# schematic.net
KiCad netlist of a schematic drawn in EAGLE
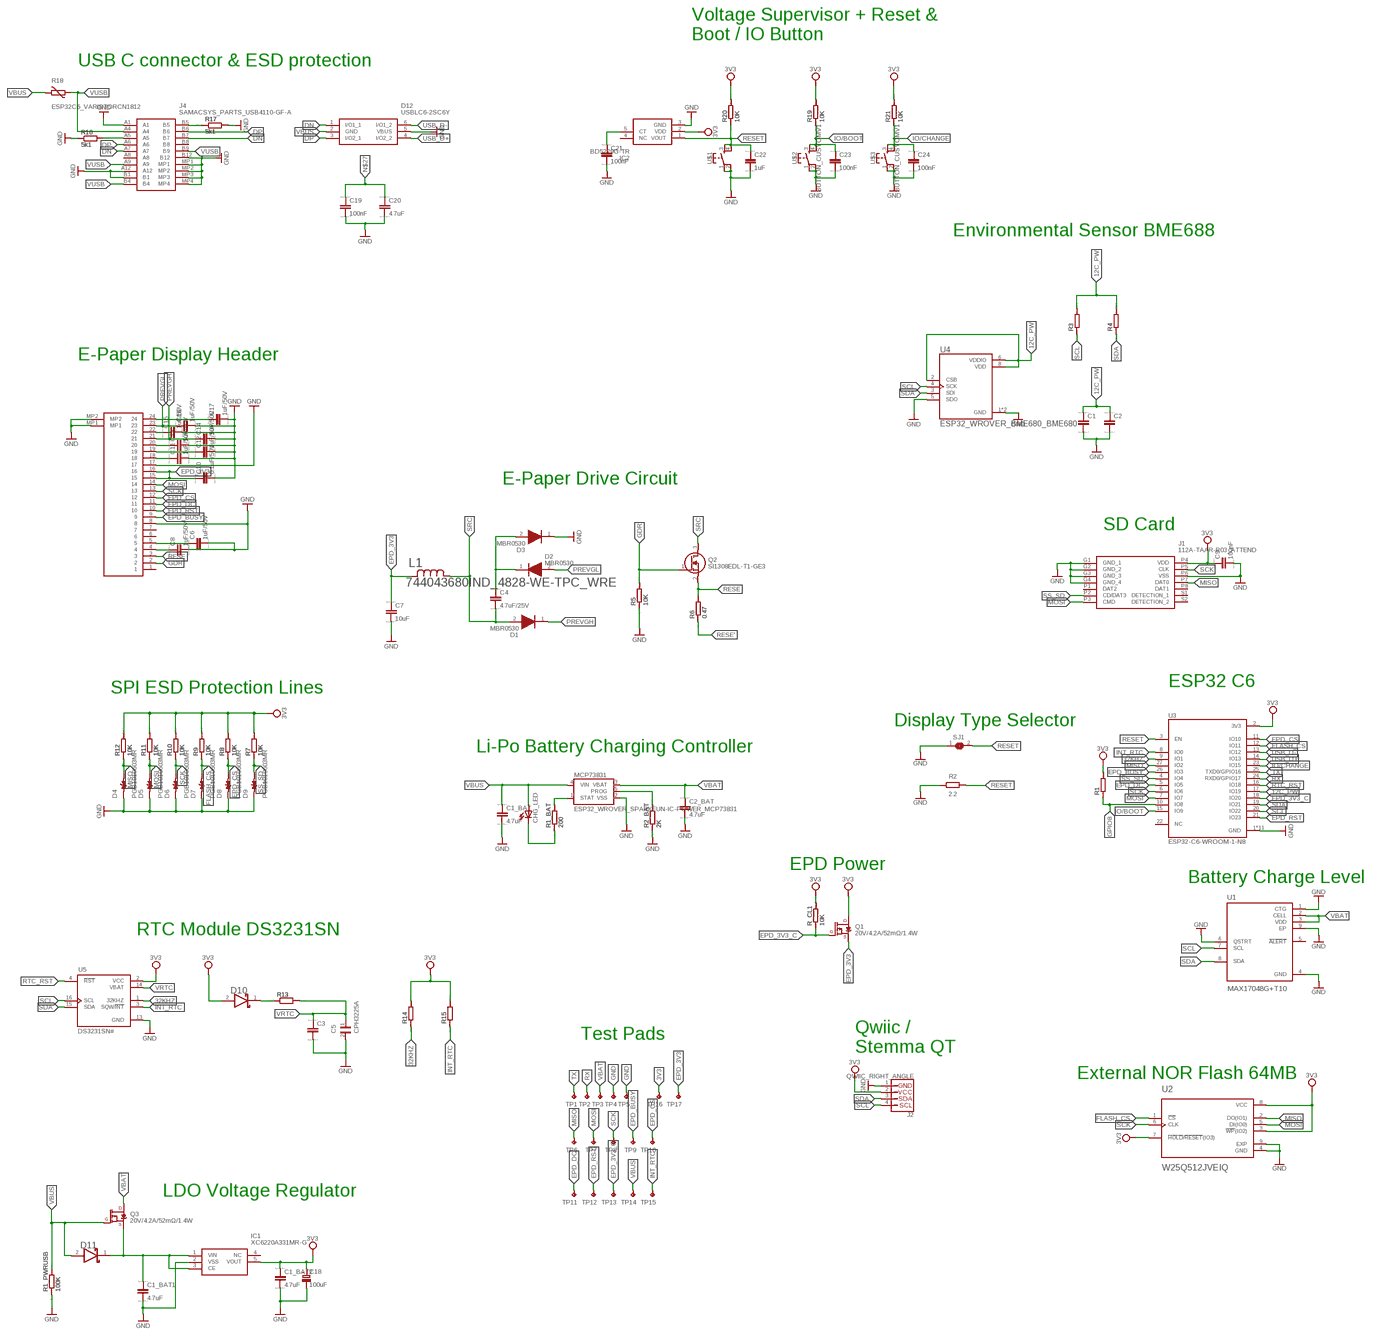
[diagram p0: schematic, sheet 1, overview]
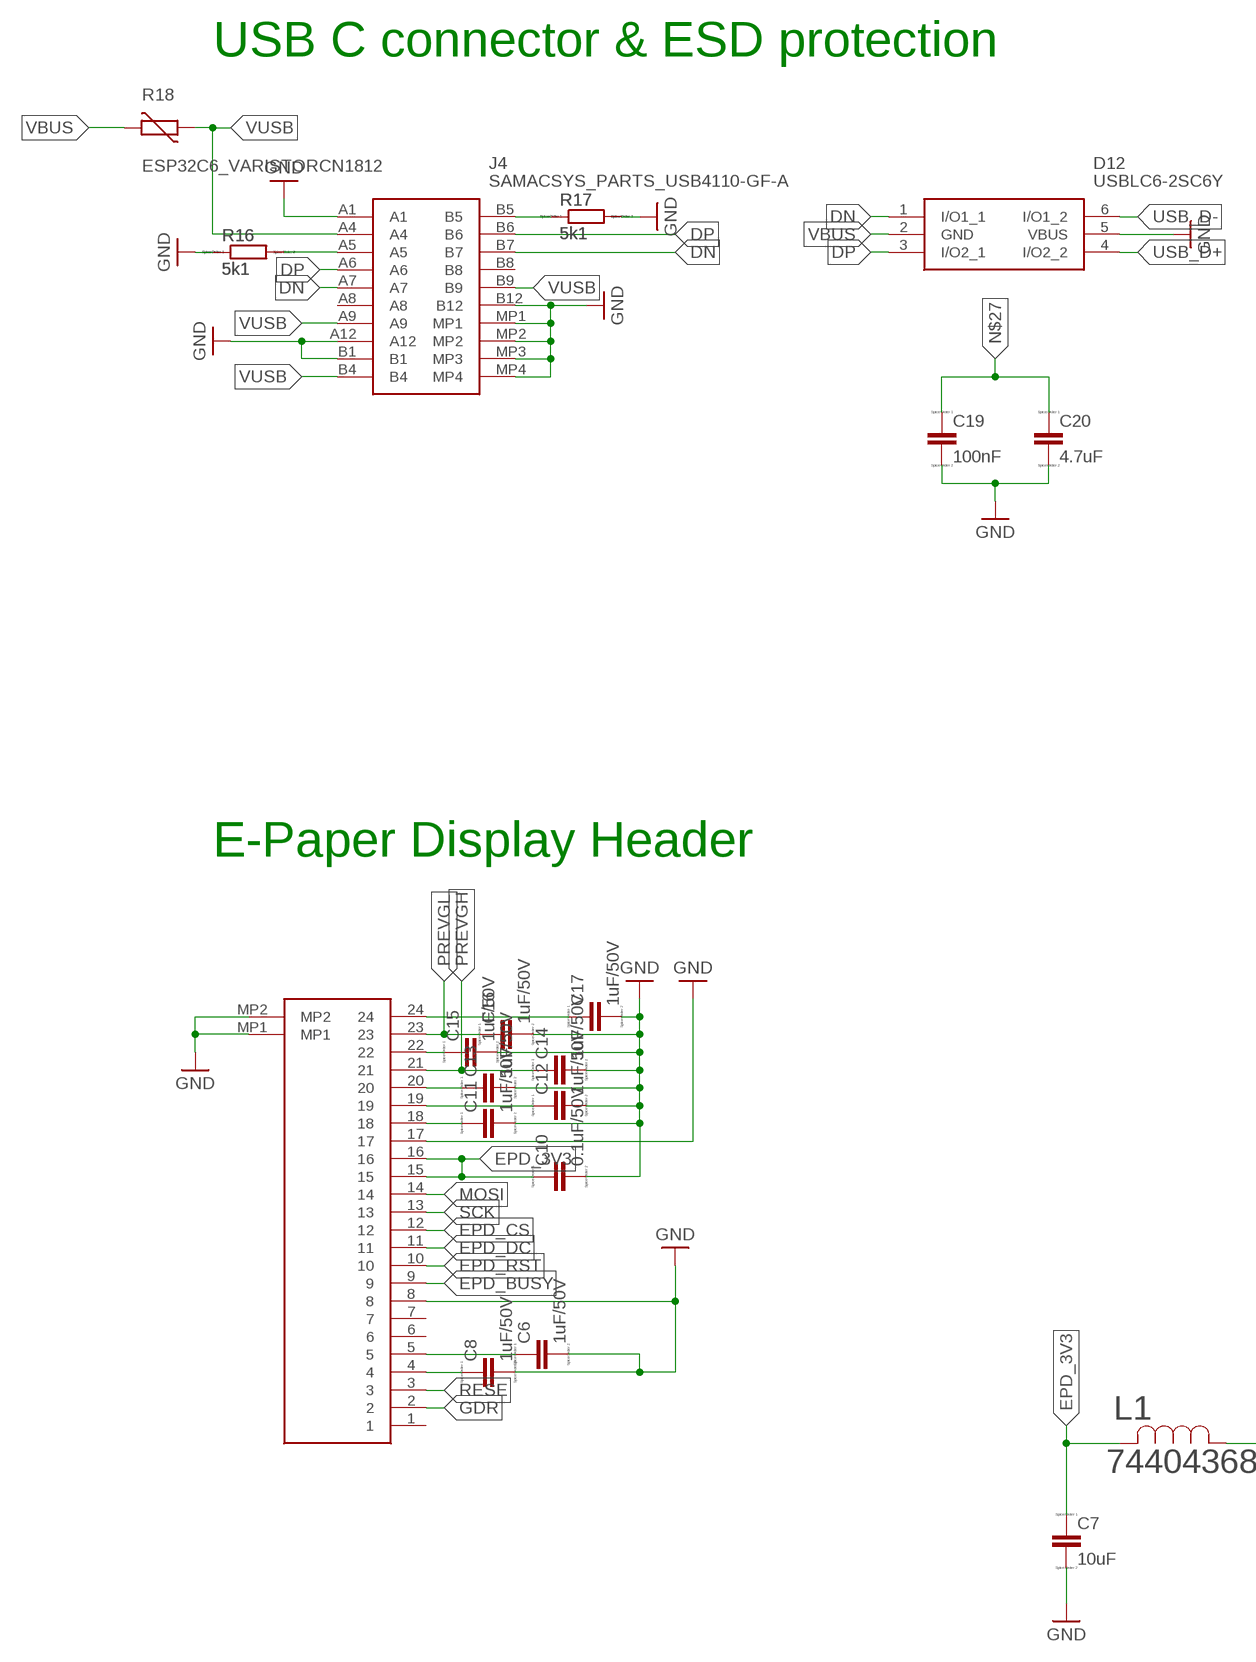
[diagram p1: schematic, sheet 1, part 1 of 4]
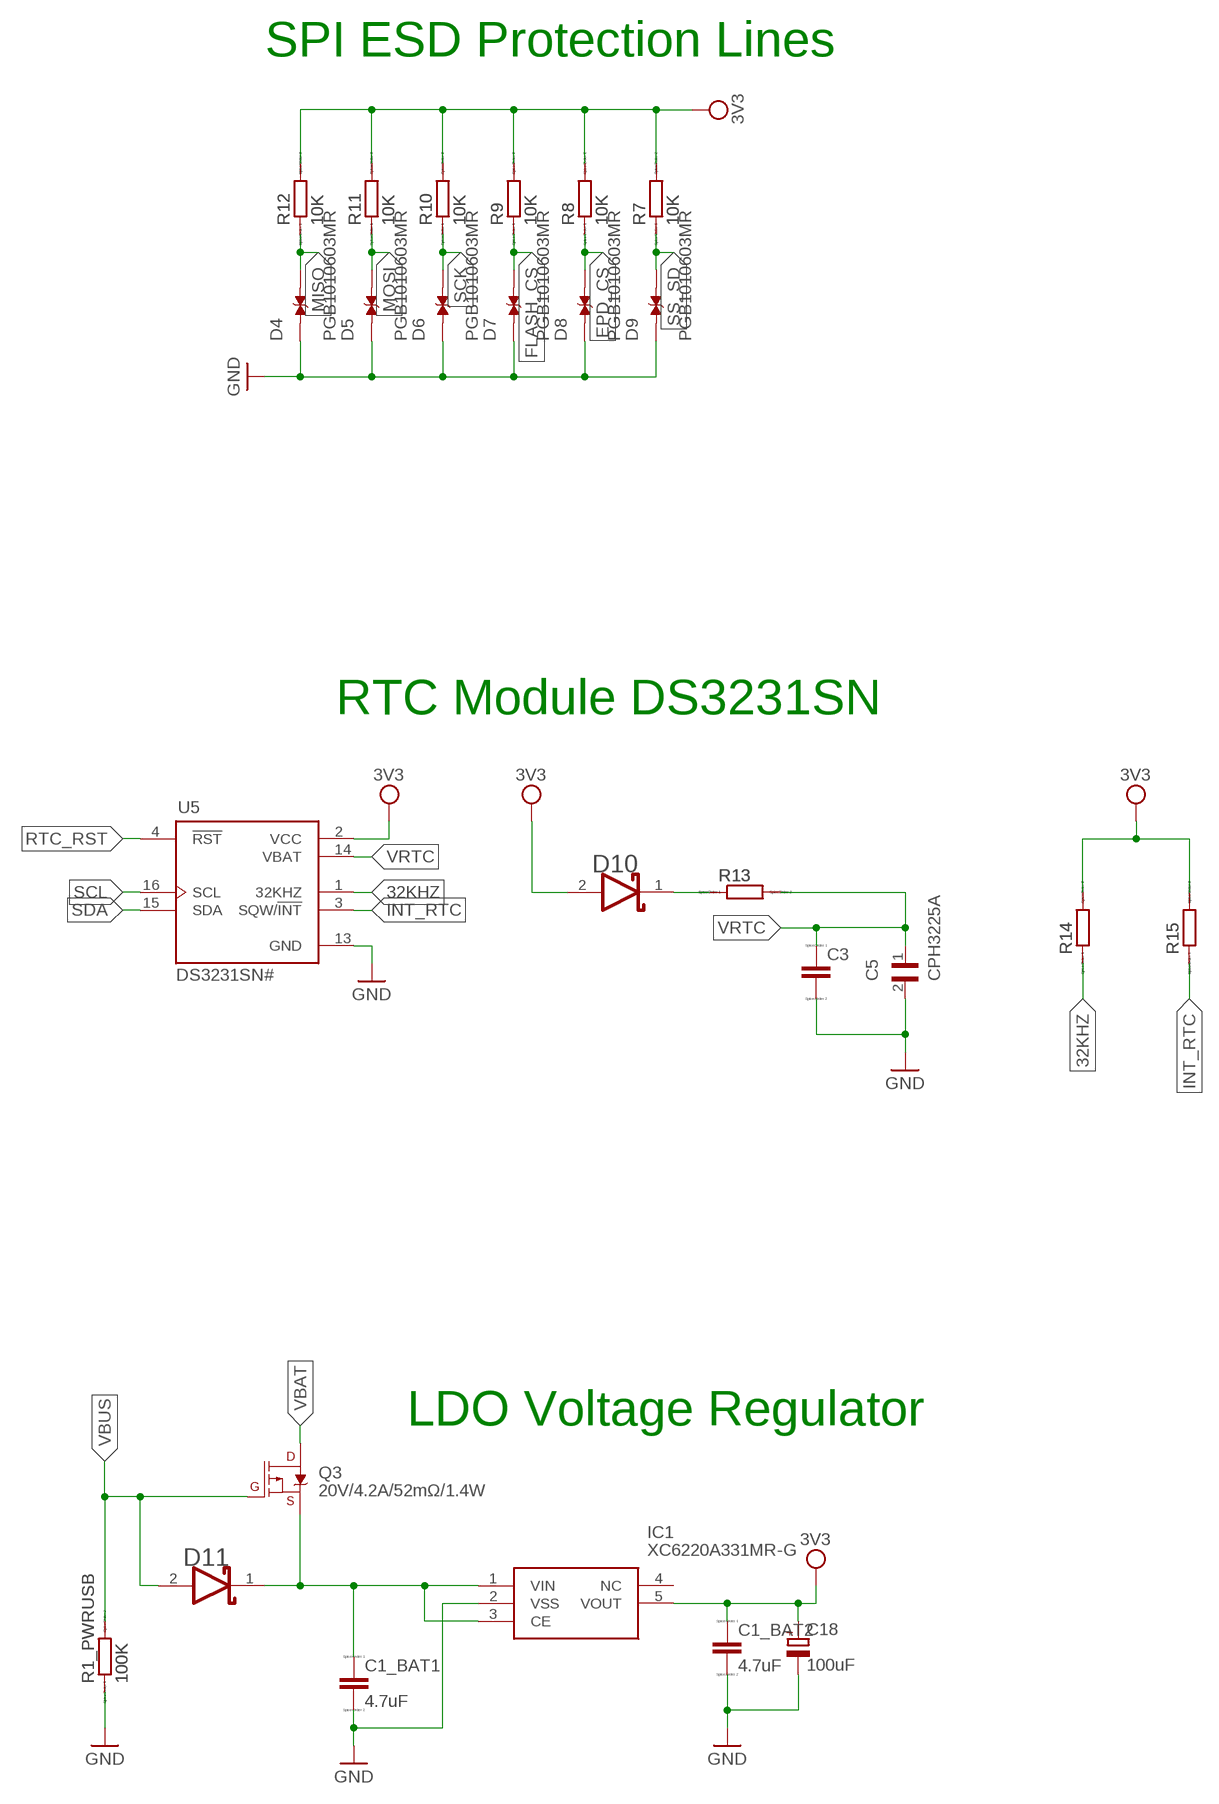
[diagram p2: schematic, sheet 1, part 2 of 4]
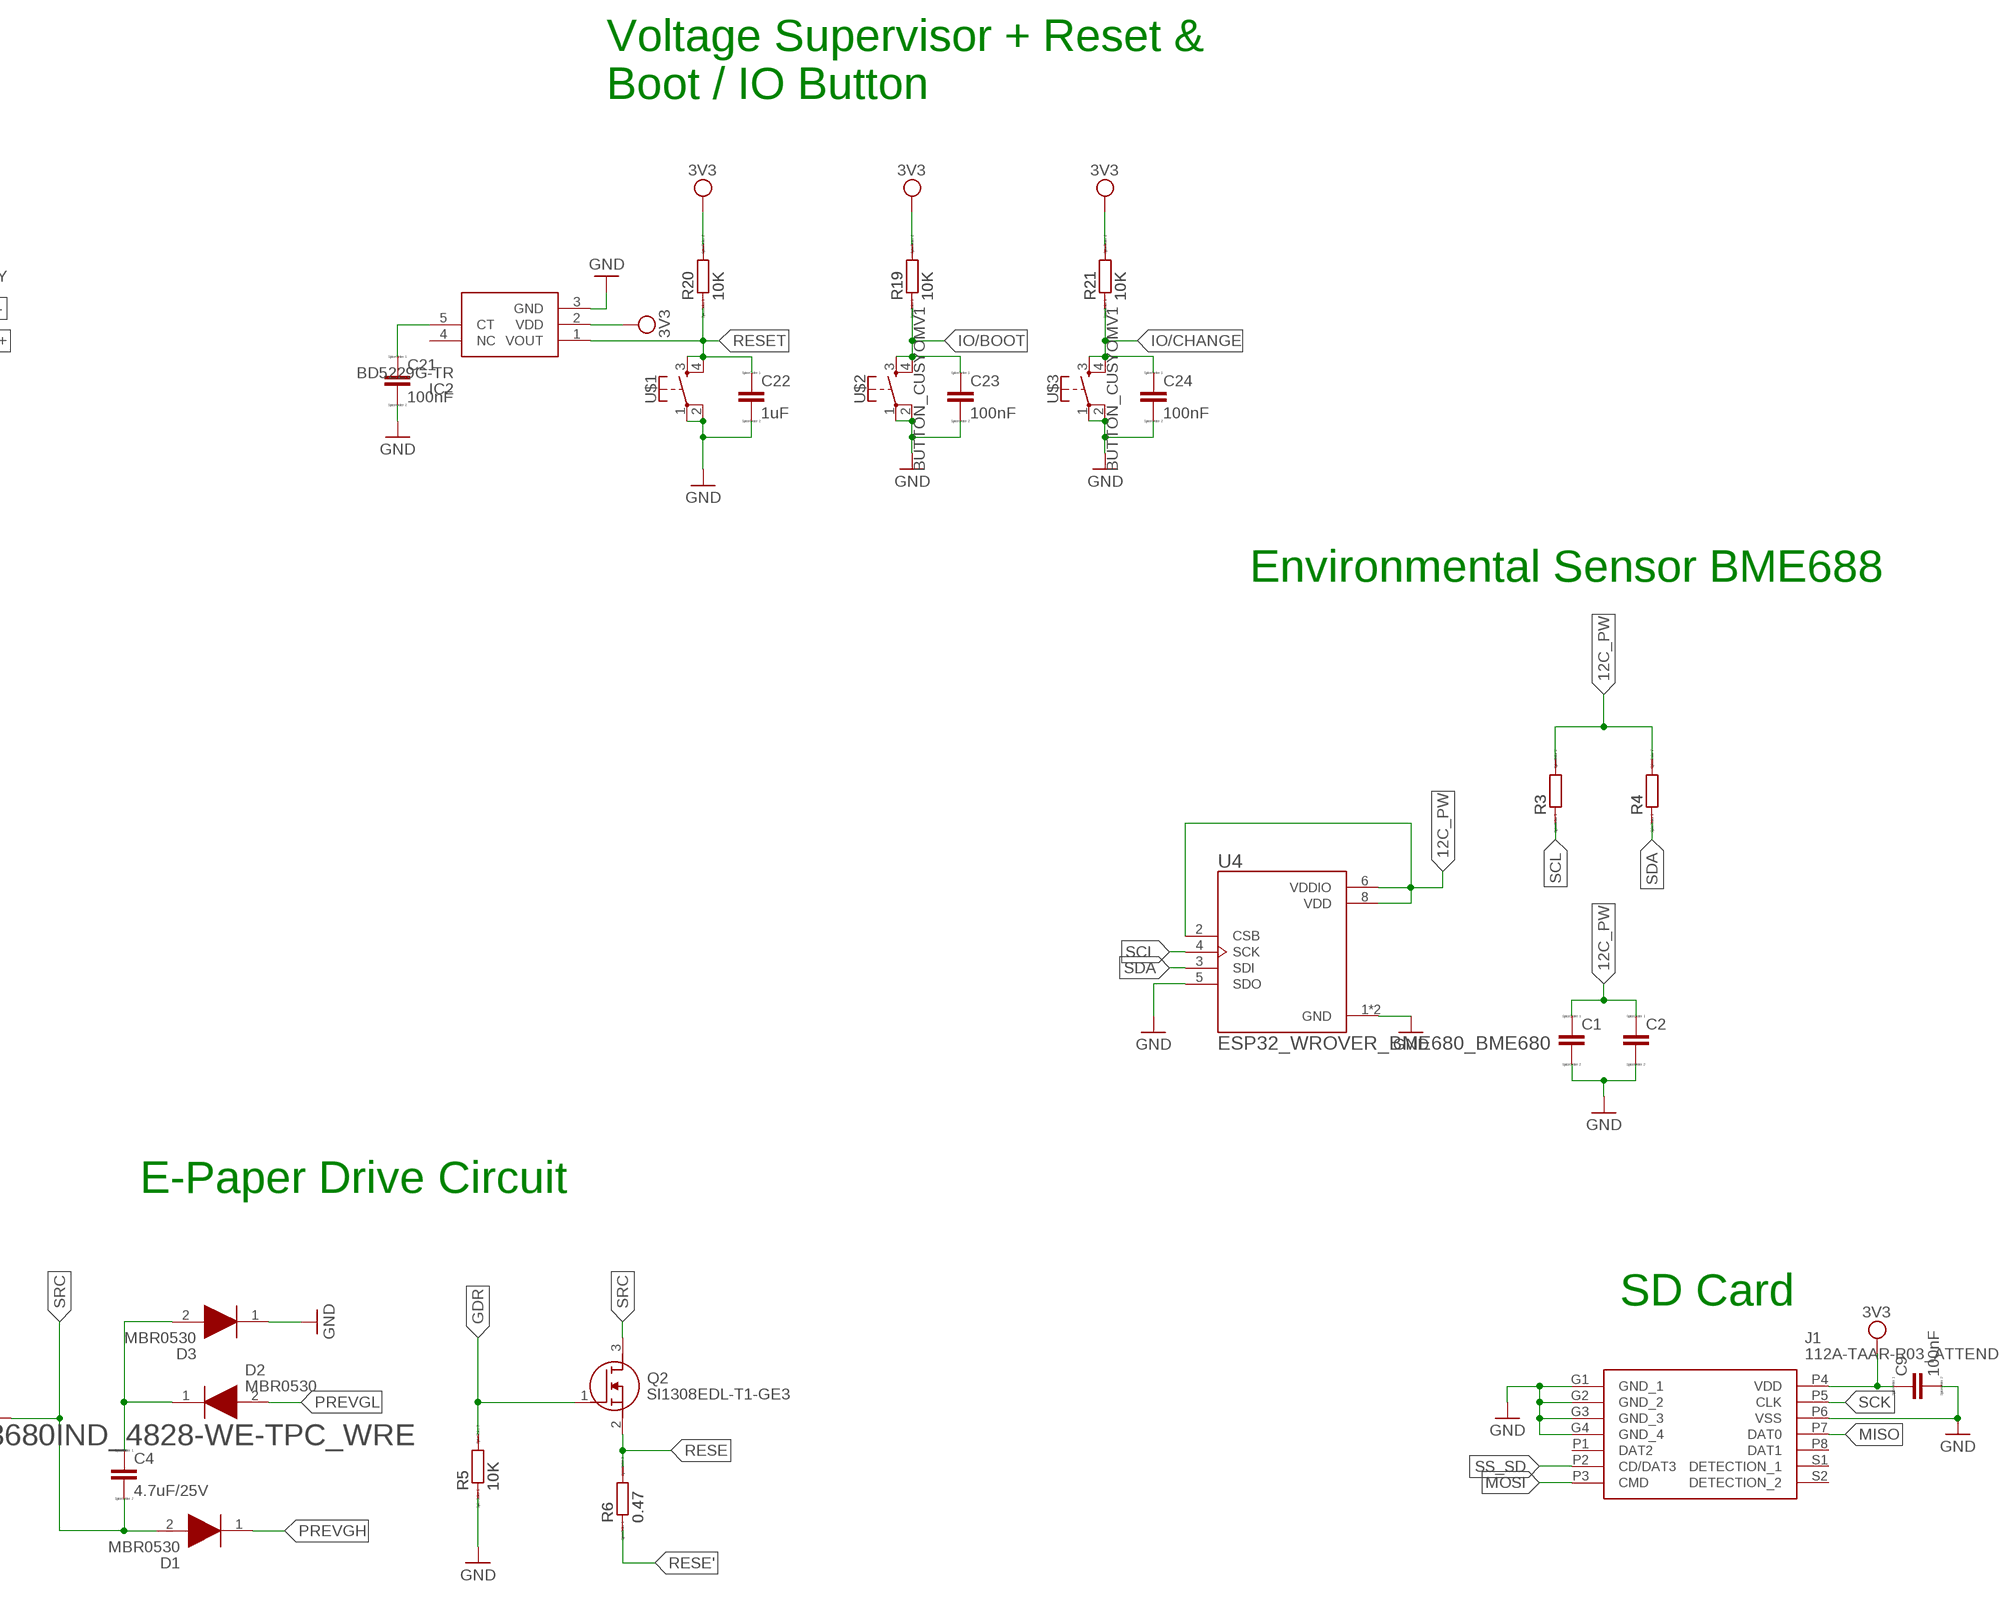
[diagram p3: schematic, sheet 1, part 3 of 4]
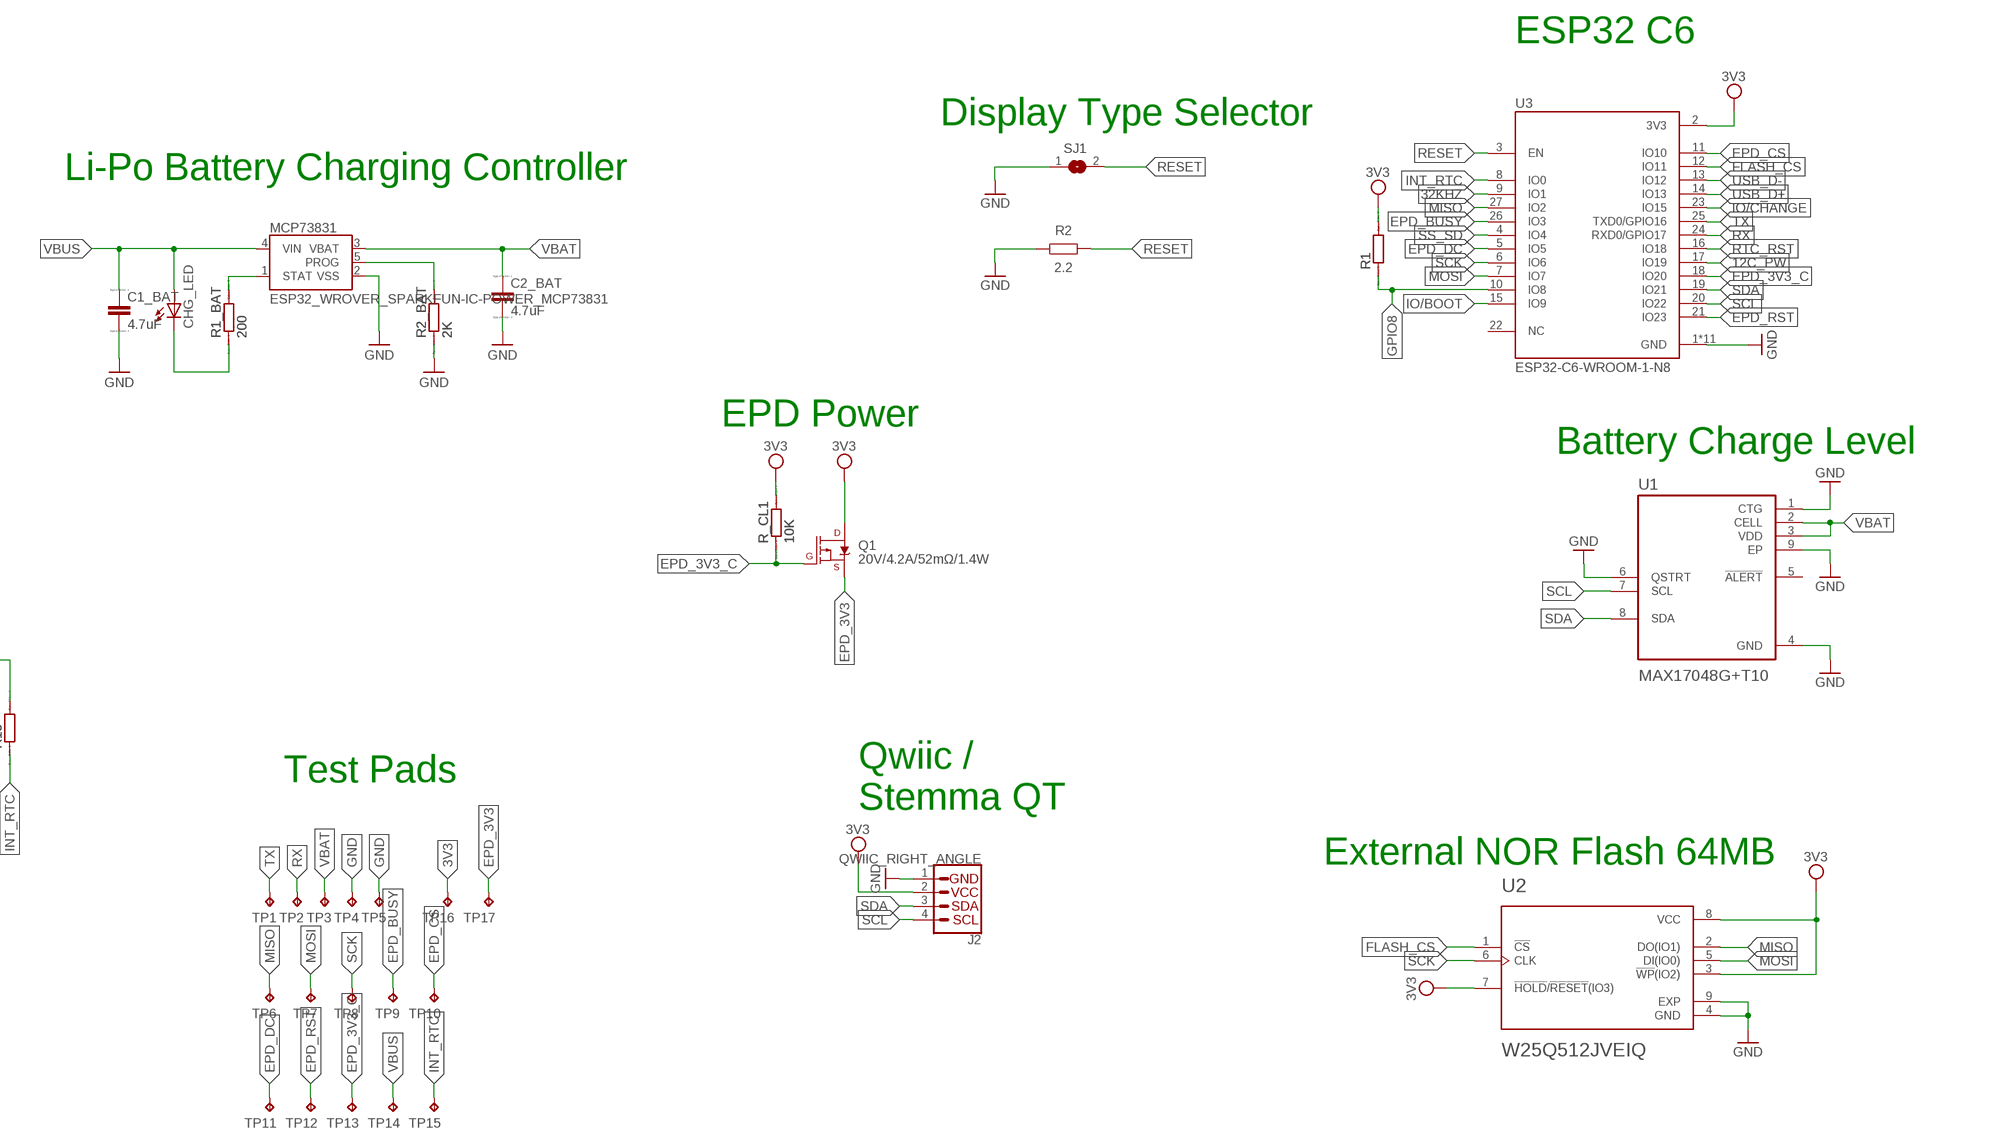
[diagram p4: schematic, sheet 1, part 4 of 4]

(export (version "E")
  (design (tool "Eeschema 10.0.6"))
  (components
    (comp (ref "C1")
      (value "ESP32_WROVER_EAGLE-LTSPICE_CC0402")
      (footprint "eagle-import:ESP32_WROVER_EAGLE-LTSPICE_C0402")
      (libsource (lib "eagle-import") (part "ESP32_WROVER_EAGLE-LTSPICE_CC0402"))
    )
    (comp (ref "C1_BAT")
      (value "4.7uF")
      (footprint "eagle-import:ESP32_WROVER_EAGLE-LTSPICE_C0402")
      (libsource (lib "eagle-import") (part "ESP32_WROVER_EAGLE-LTSPICE_CC0402"))
    )
    (comp (ref "C1_BAT1")
      (value "4.7uF")
      (footprint "eagle-import:ESP32_WROVER_EAGLE-LTSPICE_C0402")
      (libsource (lib "eagle-import") (part "ESP32_WROVER_EAGLE-LTSPICE_CC0402"))
    )
    (comp (ref "C1_BAT2")
      (value "4.7uF")
      (footprint "eagle-import:ESP32_WROVER_EAGLE-LTSPICE_C0402")
      (libsource (lib "eagle-import") (part "ESP32_WROVER_EAGLE-LTSPICE_CC0402"))
    )
    (comp (ref "C2")
      (value "ESP32_WROVER_EAGLE-LTSPICE_CC0402")
      (footprint "eagle-import:ESP32_WROVER_EAGLE-LTSPICE_C0402")
      (libsource (lib "eagle-import") (part "ESP32_WROVER_EAGLE-LTSPICE_CC0402"))
    )
    (comp (ref "C2_BAT")
      (value "4.7uF")
      (footprint "eagle-import:ESP32_WROVER_EAGLE-LTSPICE_C0402")
      (libsource (lib "eagle-import") (part "ESP32_WROVER_EAGLE-LTSPICE_CC0402"))
    )
    (comp (ref "C3")
      (value "EAGLE-LTSPICE_CC0402")
      (footprint "eagle-import:EAGLE-LTSPICE_C0402")
      (libsource (lib "eagle-import") (part "EAGLE-LTSPICE_CC0402"))
    )
    (comp (ref "C4")
      (value "4.7uF/25V")
      (footprint "eagle-import:EAGLE-LTSPICE_C0402")
      (libsource (lib "eagle-import") (part "EAGLE-LTSPICE_CC0402"))
    )
    (comp (ref "C5")
      (value "CPH3225A")
      (footprint "eagle-import:CAPCP3225X100N")
      (fields (field (name "MF") "Seiko Instruments"))
      (libsource (lib "eagle-import") (part "CPH3225A"))
    )
    (comp (ref "C6")
      (value "1uF/50V")
      (footprint "eagle-import:ESP32_WROVER_EAGLE-LTSPICE_C0402")
      (libsource (lib "eagle-import") (part "ESP32_WROVER_EAGLE-LTSPICE_CC0402"))
    )
    (comp (ref "C7")
      (value "10uF")
      (footprint "eagle-import:EAGLE-LTSPICE_C0402")
      (libsource (lib "eagle-import") (part "EAGLE-LTSPICE_CC0402"))
    )
    (comp (ref "C8")
      (value "1uF/50V")
      (footprint "eagle-import:ESP32_WROVER_EAGLE-LTSPICE_C0402")
      (libsource (lib "eagle-import") (part "ESP32_WROVER_EAGLE-LTSPICE_CC0402"))
    )
    (comp (ref "C9")
      (value "100nF")
      (footprint "eagle-import:EAGLE-LTSPICE_C0402")
      (libsource (lib "eagle-import") (part "EAGLE-LTSPICE_CC0402"))
    )
    (comp (ref "C10")
      (value "0.1uF/50V")
      (footprint "eagle-import:ESP32_WROVER_EAGLE-LTSPICE_C0402")
      (libsource (lib "eagle-import") (part "ESP32_WROVER_EAGLE-LTSPICE_CC0402"))
    )
    (comp (ref "C11")
      (value "1uF/50V")
      (footprint "eagle-import:ESP32_WROVER_EAGLE-LTSPICE_C0402")
      (libsource (lib "eagle-import") (part "ESP32_WROVER_EAGLE-LTSPICE_CC0402"))
    )
    (comp (ref "C12")
      (value "1uF/50V")
      (footprint "eagle-import:ESP32_WROVER_EAGLE-LTSPICE_C0402")
      (libsource (lib "eagle-import") (part "ESP32_WROVER_EAGLE-LTSPICE_CC0402"))
    )
    (comp (ref "C13")
      (value "1uF/50V")
      (footprint "eagle-import:ESP32_WROVER_EAGLE-LTSPICE_C0402")
      (libsource (lib "eagle-import") (part "ESP32_WROVER_EAGLE-LTSPICE_CC0402"))
    )
    (comp (ref "C14")
      (value "1uF/50V")
      (footprint "eagle-import:ESP32_WROVER_EAGLE-LTSPICE_C0402")
      (libsource (lib "eagle-import") (part "ESP32_WROVER_EAGLE-LTSPICE_CC0402"))
    )
    (comp (ref "C15")
      (value "1uF/50V")
      (footprint "eagle-import:ESP32_WROVER_EAGLE-LTSPICE_C0402")
      (libsource (lib "eagle-import") (part "ESP32_WROVER_EAGLE-LTSPICE_CC0402"))
    )
    (comp (ref "C16")
      (value "1uF/50V")
      (footprint "eagle-import:ESP32_WROVER_EAGLE-LTSPICE_C0402")
      (libsource (lib "eagle-import") (part "ESP32_WROVER_EAGLE-LTSPICE_CC0402"))
    )
    (comp (ref "C17")
      (value "1uF/50V")
      (footprint "eagle-import:ESP32_WROVER_EAGLE-LTSPICE_C0402")
      (libsource (lib "eagle-import") (part "ESP32_WROVER_EAGLE-LTSPICE_CC0402"))
    )
    (comp (ref "C18")
      (value "100uF")
      (footprint "eagle-import:RCL_CT3528")
      (libsource (lib "eagle-import") (part "RCL_CPOL-EUCT3528"))
    )
    (comp (ref "C19")
      (value "100nF")
      (footprint "eagle-import:ESP32_WROVER_EAGLE-LTSPICE_C0402")
      (libsource (lib "eagle-import") (part "ESP32_WROVER_EAGLE-LTSPICE_CC0402"))
    )
    (comp (ref "C20")
      (value "4.7uF")
      (footprint "eagle-import:ESP32_WROVER_EAGLE-LTSPICE_C0402")
      (libsource (lib "eagle-import") (part "ESP32_WROVER_EAGLE-LTSPICE_CC0402"))
    )
    (comp (ref "C21")
      (value "100nF")
      (footprint "eagle-import:ESP32_WROVER_EAGLE-LTSPICE_C0402")
      (libsource (lib "eagle-import") (part "ESP32_WROVER_EAGLE-LTSPICE_CC0402"))
    )
    (comp (ref "C22")
      (value "1uF")
      (footprint "eagle-import:ESP32_WROVER_EAGLE-LTSPICE_C0402")
      (libsource (lib "eagle-import") (part "ESP32_WROVER_EAGLE-LTSPICE_CC0402"))
    )
    (comp (ref "C23")
      (value "100nF")
      (footprint "eagle-import:ESP32_WROVER_EAGLE-LTSPICE_C0402")
      (libsource (lib "eagle-import") (part "ESP32_WROVER_EAGLE-LTSPICE_CC0402"))
    )
    (comp (ref "C24")
      (value "100nF")
      (footprint "eagle-import:ESP32_WROVER_EAGLE-LTSPICE_C0402")
      (libsource (lib "eagle-import") (part "ESP32_WROVER_EAGLE-LTSPICE_CC0402"))
    )
    (comp (ref "CHG_LED")
      (value "ADAFRUIT_LEDCHIP-LED0603")
      (footprint "eagle-import:ADAFRUIT_CHIP-LED0603")
      (libsource (lib "eagle-import") (part "ADAFRUIT_LEDCHIP-LED0603"))
    )
    (comp (ref "D1")
      (value "MBR0530")
      (footprint "eagle-import:SOD3716X135N")
      (fields (field (name "MF") "ON Semiconductor"))
      (libsource (lib "eagle-import") (part "MBR0530"))
    )
    (comp (ref "D2")
      (value "MBR0530")
      (footprint "eagle-import:SOD3716X135N")
      (fields (field (name "MF") "ON Semiconductor"))
      (libsource (lib "eagle-import") (part "MBR0530"))
    )
    (comp (ref "D3")
      (value "MBR0530")
      (footprint "eagle-import:SOD3716X135N")
      (fields (field (name "MF") "ON Semiconductor"))
      (libsource (lib "eagle-import") (part "MBR0530"))
    )
    (comp (ref "D4")
      (value "PGB1010603MR")
      (footprint "eagle-import:DIOC1608X36N")
      (fields (field (name "MF") "Littelfuse Inc."))
      (libsource (lib "eagle-import") (part "PGB1010603MR"))
    )
    (comp (ref "D5")
      (value "PGB1010603MR")
      (footprint "eagle-import:DIOC1608X36N")
      (fields (field (name "MF") "Littelfuse Inc."))
      (libsource (lib "eagle-import") (part "PGB1010603MR"))
    )
    (comp (ref "D6")
      (value "PGB1010603MR")
      (footprint "eagle-import:DIOC1608X36N")
      (fields (field (name "MF") "Littelfuse Inc."))
      (libsource (lib "eagle-import") (part "PGB1010603MR"))
    )
    (comp (ref "D7")
      (value "PGB1010603MR")
      (footprint "eagle-import:DIOC1608X36N")
      (fields (field (name "MF") "Littelfuse Inc."))
      (libsource (lib "eagle-import") (part "PGB1010603MR"))
    )
    (comp (ref "D8")
      (value "PGB1010603MR")
      (footprint "eagle-import:DIOC1608X36N")
      (fields (field (name "MF") "Littelfuse Inc."))
      (libsource (lib "eagle-import") (part "PGB1010603MR"))
    )
    (comp (ref "D9")
      (value "PGB1010603MR")
      (footprint "eagle-import:DIOC1608X36N")
      (fields (field (name "MF") "Littelfuse Inc."))
      (libsource (lib "eagle-import") (part "PGB1010603MR"))
    )
    (comp (ref "D10")
      (value "ESP32_WROVER_AVX---SD0805S020S1R0_AVX_SD0805S020S1R0_0_0AVX_SD0805S020S1R0_0_0")
      (footprint "eagle-import:ESP32_WROVER_AVX---SD0805S020S1R0_AVX_SD0805S020S1R0_0")
      (fields
        (field (name "DIGIKEY_PART_NUMBER") "478-7800-1-ND")
        (field (name "MF") "AVX")
        (field (name "MOUSER_PART_NUMBER") "581-SD0805S020S1R0")
      )
      (libsource (lib "eagle-import") (part "ESP32_WROVER_AVX---SD0805S020S1R0_AVX_SD0805S020S1R0_0_0AVX_SD0805S020S1R0_0_0"))
    )
    (comp (ref "D11")
      (value "ESP32_WROVER_AVX---SD0805S020S1R0_AVX_SD0805S020S1R0_0_0AVX_SD0805S020S1R0_0_0")
      (footprint "eagle-import:ESP32_WROVER_AVX---SD0805S020S1R0_AVX_SD0805S020S1R0_0")
      (fields
        (field (name "DIGIKEY_PART_NUMBER") "478-7800-1-ND")
        (field (name "MF") "AVX")
        (field (name "MOUSER_PART_NUMBER") "581-SD0805S020S1R0")
      )
      (libsource (lib "eagle-import") (part "ESP32_WROVER_AVX---SD0805S020S1R0_AVX_SD0805S020S1R0_0_0AVX_SD0805S020S1R0_0_0"))
    )
    (comp (ref "D12")
      (value "USBLC6-2SC6Y")
      (footprint "eagle-import:SOT95P280X145-6N")
      (fields (field (name "MF") "STMicroelectronics"))
      (libsource (lib "eagle-import") (part "USBLC6-2SC6Y"))
    )
    (comp (ref "IC1")
      (value "XC6220A331MR-G")
      (footprint "eagle-import:SOT95P280X120-5N")
      (fields (field (name "MOUSER_PART_NUMBER") "865-XC6220A331MR-G"))
      (libsource (lib "eagle-import") (part "XC6220A331MR-G"))
    )
    (comp (ref "IC2")
      (value "BD5229G-TR")
      (footprint "eagle-import:SOT95P280X125-5N")
      (fields (field (name "MOUSER_PART_NUMBER") "755-BD5229G-TR"))
      (libsource (lib "eagle-import") (part "BD5229G-TR"))
    )
    (comp (ref "J1")
      (value "112A-TAAR-R03_ATTEND")
      (footprint "eagle-import:112ATAARR03ATTEND")
      (fields (field (name "MANUFACTURER_PART_NUMBER") "112A-TAAR-R03 ATTEND"))
      (libsource (lib "eagle-import") (part "112A-TAAR-R03_ATTEND"))
    )
    (comp (ref "J2")
      (value "QWIIC_RIGHT_ANGLE")
      (footprint "eagle-import:JST04_1MM_RA")
      (libsource (lib "eagle-import") (part "QWIIC_CONNECTORJS-1MM"))
    )
    (comp (ref "J3")
      (value "FH34SRJ-24S-0.5SH_99_")
      (footprint "eagle-import:FH34SRJ24S05SH99")
      (fields
        (field (name "MANUFACTURER_PART_NUMBER") "FH34SRJ-24S-0.5SH(99)")
        (field (name "MOUSER_PART_NUMBER") "798-FH34SRJ24S05SH99")
      )
      (libsource (lib "eagle-import") (part "FH34SRJ-24S-0.5SH_99_"))
    )
    (comp (ref "J4")
      (value "SAMACSYS_PARTS_USB4110-GF-A")
      (footprint "eagle-import:SAMACSYS_PARTS_USB4110GFA")
      (fields
        (field (name "MANUFACTURER_PART_NUMBER") "USB4110-GF-A")
        (field (name "MOUSER_PART_NUMBER") "640-USB4110-GF-A")
      )
      (libsource (lib "eagle-import") (part "SAMACSYS_PARTS_USB4110-GF-A"))
    )
    (comp (ref "L1")
      (value "744043680IND_4828-WE-TPC_WRE")
      (footprint "eagle-import:IND_4828-WE-TPC_WRE")
      (fields
        (field (name "MANUFACTURER_PART_NUMBER") "744043680")
        (field (name "COPYRIGHT") "Copyright (C) 2024 Ultra Librarian. All rights reserved.")
      )
      (libsource (lib "eagle-import") (part "744043680IND_4828-WE-TPC_WRE"))
    )
    (comp (ref "MCP73831")
      (value "ESP32_WROVER_SPARKFUN-IC-POWER_MCP73831")
      (footprint "eagle-import:ESP32_WROVER_SPARKFUN-IC-POWER_SOT23-5")
      (libsource (lib "eagle-import") (part "ESP32_WROVER_SPARKFUN-IC-POWER_MCP73831"))
    )
    (comp (ref "Q1")
      (value "20V/4.2A/52mΩ/1.4W")
      (footprint "eagle-import:ESP32_WROVER_SPARKFUN-DISCRETESEMI_SOT23-3")
      (libsource (lib "eagle-import") (part "ESP32_WROVER_SPARKFUN-DISCRETESEMI_MOSFET_PCH-DMG2305UX-7"))
    )
    (comp (ref "Q2")
      (value "SI1308EDL-T1-GE3")
      (footprint "eagle-import:SOT65P210X110-3N")
      (fields (field (name "MF") "Vishay Siliconix"))
      (libsource (lib "eagle-import") (part "SI1308EDL-T1-GE3"))
    )
    (comp (ref "Q3")
      (value "20V/4.2A/52mΩ/1.4W")
      (footprint "eagle-import:ESP32_WROVER_SPARKFUN-DISCRETESEMI_SOT23-3")
      (libsource (lib "eagle-import") (part "ESP32_WROVER_SPARKFUN-DISCRETESEMI_MOSFET_PCH-DMG2305UX-7"))
    )
    (comp (ref "R1")
      (value "ESP32_WROVER_EAGLE-LTSPICE_RR0402")
      (footprint "eagle-import:ESP32_WROVER_EAGLE-LTSPICE_R0402")
      (libsource (lib "eagle-import") (part "ESP32_WROVER_EAGLE-LTSPICE_RR0402"))
    )
    (comp (ref "R1_BAT")
      (value "200")
      (footprint "eagle-import:ESP32_WROVER_EAGLE-LTSPICE_R0402")
      (libsource (lib "eagle-import") (part "ESP32_WROVER_EAGLE-LTSPICE_RR0402"))
    )
    (comp (ref "R1_PWRUSB")
      (value "100K")
      (footprint "eagle-import:ESP32_WROVER_EAGLE-LTSPICE_R0402")
      (libsource (lib "eagle-import") (part "ESP32_WROVER_EAGLE-LTSPICE_RR0402"))
    )
    (comp (ref "R2")
      (value "2.2")
      (footprint "eagle-import:RESC1005X40")
      (libsource (lib "eagle-import") (part "RCHIP-0402(1005-METRIC)_"))
    )
    (comp (ref "R2_BAT")
      (value "2K")
      (footprint "eagle-import:ESP32_WROVER_EAGLE-LTSPICE_R0402")
      (libsource (lib "eagle-import") (part "ESP32_WROVER_EAGLE-LTSPICE_RR0402"))
    )
    (comp (ref "R3")
      (value "ESP32_WROVER_EAGLE-LTSPICE_RR0402")
      (footprint "eagle-import:ESP32_WROVER_EAGLE-LTSPICE_R0402")
      (libsource (lib "eagle-import") (part "ESP32_WROVER_EAGLE-LTSPICE_RR0402"))
    )
    (comp (ref "R4")
      (value "ESP32_WROVER_EAGLE-LTSPICE_RR0402")
      (footprint "eagle-import:ESP32_WROVER_EAGLE-LTSPICE_R0402")
      (libsource (lib "eagle-import") (part "ESP32_WROVER_EAGLE-LTSPICE_RR0402"))
    )
    (comp (ref "R5")
      (value "10K")
      (footprint "eagle-import:ESP32_WROVER_EAGLE-LTSPICE_R0402")
      (libsource (lib "eagle-import") (part "ESP32_WROVER_EAGLE-LTSPICE_RR0402"))
    )
    (comp (ref "R6")
      (value "0.47")
      (footprint "eagle-import:ESP32_WROVER_EAGLE-LTSPICE_R0402")
      (libsource (lib "eagle-import") (part "ESP32_WROVER_EAGLE-LTSPICE_RR0402"))
    )
    (comp (ref "R7")
      (value "10K")
      (footprint "eagle-import:ESP32_WROVER_EAGLE-LTSPICE_R0402")
      (libsource (lib "eagle-import") (part "ESP32_WROVER_EAGLE-LTSPICE_RR0402"))
    )
    (comp (ref "R8")
      (value "10K")
      (footprint "eagle-import:ESP32_WROVER_EAGLE-LTSPICE_R0402")
      (libsource (lib "eagle-import") (part "ESP32_WROVER_EAGLE-LTSPICE_RR0402"))
    )
    (comp (ref "R9")
      (value "10K")
      (footprint "eagle-import:ESP32_WROVER_EAGLE-LTSPICE_R0402")
      (libsource (lib "eagle-import") (part "ESP32_WROVER_EAGLE-LTSPICE_RR0402"))
    )
    (comp (ref "R10")
      (value "10K")
      (footprint "eagle-import:ESP32_WROVER_EAGLE-LTSPICE_R0402")
      (libsource (lib "eagle-import") (part "ESP32_WROVER_EAGLE-LTSPICE_RR0402"))
    )
    (comp (ref "R11")
      (value "10K")
      (footprint "eagle-import:ESP32_WROVER_EAGLE-LTSPICE_R0402")
      (libsource (lib "eagle-import") (part "ESP32_WROVER_EAGLE-LTSPICE_RR0402"))
    )
    (comp (ref "R12")
      (value "10K")
      (footprint "eagle-import:ESP32_WROVER_EAGLE-LTSPICE_R0402")
      (libsource (lib "eagle-import") (part "ESP32_WROVER_EAGLE-LTSPICE_RR0402"))
    )
    (comp (ref "R13")
      (value "ESP32_WROVER_EAGLE-LTSPICE_RR0402")
      (footprint "eagle-import:ESP32_WROVER_EAGLE-LTSPICE_R0402")
      (libsource (lib "eagle-import") (part "ESP32_WROVER_EAGLE-LTSPICE_RR0402"))
    )
    (comp (ref "R14")
      (value "ESP32_WROVER_EAGLE-LTSPICE_RR0402")
      (footprint "eagle-import:ESP32_WROVER_EAGLE-LTSPICE_R0402")
      (libsource (lib "eagle-import") (part "ESP32_WROVER_EAGLE-LTSPICE_RR0402"))
    )
    (comp (ref "R15")
      (value "ESP32_WROVER_EAGLE-LTSPICE_RR0402")
      (footprint "eagle-import:ESP32_WROVER_EAGLE-LTSPICE_R0402")
      (libsource (lib "eagle-import") (part "ESP32_WROVER_EAGLE-LTSPICE_RR0402"))
    )
    (comp (ref "R16")
      (value "5k1")
      (footprint "eagle-import:ESP32_WROVER_EAGLE-LTSPICE_R0402")
      (libsource (lib "eagle-import") (part "ESP32_WROVER_EAGLE-LTSPICE_RR0402"))
    )
    (comp (ref "R17")
      (value "5k1")
      (footprint "eagle-import:ESP32_WROVER_EAGLE-LTSPICE_R0402")
      (libsource (lib "eagle-import") (part "ESP32_WROVER_EAGLE-LTSPICE_RR0402"))
    )
    (comp (ref "R18")
      (value "ESP32C6_VARISTORCN1812")
      (footprint "eagle-import:ESP32C6_VARISTOR_CT_CN1812")
      (libsource (lib "eagle-import") (part "ESP32C6_VARISTORCN1812"))
    )
    (comp (ref "R19")
      (value "10K")
      (footprint "eagle-import:ESP32_WROVER_EAGLE-LTSPICE_R0402")
      (libsource (lib "eagle-import") (part "ESP32_WROVER_EAGLE-LTSPICE_RR0402"))
    )
    (comp (ref "R20")
      (value "10K")
      (footprint "eagle-import:ESP32_WROVER_EAGLE-LTSPICE_R0402")
      (libsource (lib "eagle-import") (part "ESP32_WROVER_EAGLE-LTSPICE_RR0402"))
    )
    (comp (ref "R21")
      (value "10K")
      (footprint "eagle-import:ESP32_WROVER_EAGLE-LTSPICE_R0402")
      (libsource (lib "eagle-import") (part "ESP32_WROVER_EAGLE-LTSPICE_RR0402"))
    )
    (comp (ref "R_CL1")
      (value "10K")
      (footprint "eagle-import:ESP32_WROVER_EAGLE-LTSPICE_R0402")
      (libsource (lib "eagle-import") (part "ESP32_WROVER_EAGLE-LTSPICE_RR0402"))
    )
    (comp (ref "SJ1") (value "SJ") (footprint "eagle-import:SJ") (libsource (lib "eagle-import") (part "SJ")))
    (comp (ref "TP1")
      (value "TPTP20R")
      (footprint "eagle-import:TP20R")
      (libsource (lib "eagle-import") (part "DeskAssistant v19 v1_vf.QlMnSdWeTriAZttPZU_4VQ_TPTP20R"))
    )
    (comp (ref "TP2")
      (value "TPTP20R")
      (footprint "eagle-import:TP20R")
      (libsource (lib "eagle-import") (part "DeskAssistant v19 v1_vf.QlMnSdWeTriAZttPZU_4VQ_TPTP20R"))
    )
    (comp (ref "TP3")
      (value "TPTP20R")
      (footprint "eagle-import:TP20R")
      (libsource (lib "eagle-import") (part "DeskAssistant v19 v1_vf.QlMnSdWeTriAZttPZU_4VQ_TPTP20R"))
    )
    (comp (ref "TP4")
      (value "TPTP20R")
      (footprint "eagle-import:TP20R")
      (libsource (lib "eagle-import") (part "DeskAssistant v19 v1_vf.QlMnSdWeTriAZttPZU_4VQ_TPTP20R"))
    )
    (comp (ref "TP5")
      (value "TPTP20R")
      (footprint "eagle-import:TP20R")
      (libsource (lib "eagle-import") (part "DeskAssistant v19 v1_vf.QlMnSdWeTriAZttPZU_4VQ_TPTP20R"))
    )
    (comp (ref "TP6")
      (value "TPTP20R")
      (footprint "eagle-import:TP20R")
      (libsource (lib "eagle-import") (part "DeskAssistant v19 v1_vf.QlMnSdWeTriAZttPZU_4VQ_TPTP20R"))
    )
    (comp (ref "TP7")
      (value "TPTP20R")
      (footprint "eagle-import:TP20R")
      (libsource (lib "eagle-import") (part "DeskAssistant v19 v1_vf.QlMnSdWeTriAZttPZU_4VQ_TPTP20R"))
    )
    (comp (ref "TP8")
      (value "TPTP20R")
      (footprint "eagle-import:TP20R")
      (libsource (lib "eagle-import") (part "TPTP20R"))
    )
    (comp (ref "TP9")
      (value "TPTP20R")
      (footprint "eagle-import:TP20R")
      (libsource (lib "eagle-import") (part "DeskAssistant v19 v1_vf.QlMnSdWeTriAZttPZU_4VQ_TPTP20R"))
    )
    (comp (ref "TP10")
      (value "TPTP20R")
      (footprint "eagle-import:TP20R")
      (libsource (lib "eagle-import") (part "DeskAssistant v19 v1_vf.QlMnSdWeTriAZttPZU_4VQ_TPTP20R"))
    )
    (comp (ref "TP11")
      (value "TPTP20R")
      (footprint "eagle-import:TP20R")
      (libsource (lib "eagle-import") (part "DeskAssistant v19 v1_vf.QlMnSdWeTriAZttPZU_4VQ_TPTP20R"))
    )
    (comp (ref "TP12")
      (value "TPTP20R")
      (footprint "eagle-import:TP20R")
      (libsource (lib "eagle-import") (part "DeskAssistant v19 v1_vf.QlMnSdWeTriAZttPZU_4VQ_TPTP20R"))
    )
    (comp (ref "TP13")
      (value "TPTP20R")
      (footprint "eagle-import:TP20R")
      (libsource (lib "eagle-import") (part "DeskAssistant v19 v1_vf.QlMnSdWeTriAZttPZU_4VQ_TPTP20R"))
    )
    (comp (ref "TP14")
      (value "TPTP20R")
      (footprint "eagle-import:TP20R")
      (libsource (lib "eagle-import") (part "DeskAssistant v19 v1_vf.QlMnSdWeTriAZttPZU_4VQ_TPTP20R"))
    )
    (comp (ref "TP15")
      (value "TPTP20R")
      (footprint "eagle-import:TP20R")
      (libsource (lib "eagle-import") (part "DeskAssistant v19 v1_vf.QlMnSdWeTriAZttPZU_4VQ_TPTP20R"))
    )
    (comp (ref "TP16")
      (value "TPTP20R")
      (footprint "eagle-import:TP20R")
      (libsource (lib "eagle-import") (part "DeskAssistant v19 v1_vf.QlMnSdWeTriAZttPZU_4VQ_TPTP20R"))
    )
    (comp (ref "TP17")
      (value "TPTP20R")
      (footprint "eagle-import:TP20R")
      (libsource (lib "eagle-import") (part "TPTP20R"))
    )
    (comp (ref "U$1")
      (value "BUTTON_CUSYOMV1")
      (footprint "eagle-import:MYBUTTON")
      (libsource (lib "eagle-import") (part "BUTTON_CUSYOMV1"))
    )
    (comp (ref "U$2")
      (value "BUTTON_CUSYOMV1")
      (footprint "eagle-import:MYBUTTON")
      (libsource (lib "eagle-import") (part "BUTTON_CUSYOMV1"))
    )
    (comp (ref "U$3")
      (value "BUTTON_CUSYOMV1")
      (footprint "eagle-import:MYBUTTON")
      (libsource (lib "eagle-import") (part "BUTTON_CUSYOMV1"))
    )
    (comp (ref "U1")
      (value "MAX17048G+T10")
      (footprint "eagle-import:SON50P200X200X80-9N")
      (fields (field (name "MF") "Analog Devices"))
      (libsource (lib "eagle-import") (part "MAX17048G+T10"))
    )
    (comp (ref "U2")
      (value "W25Q512JVEIQ")
      (footprint "eagle-import:SON127P600X800X80-9N")
      (fields (field (name "MF") "Winbond Electronics"))
      (libsource (lib "eagle-import") (part "W25Q512JVEIQ"))
    )
    (comp (ref "U3")
      (value "ESP32-C6-WROOM-1-N8")
      (footprint "eagle-import:XCVR_ESP32-C6-WROOM-1-N8")
      (fields (field (name "MF") "Espressif Systems"))
      (libsource (lib "eagle-import") (part "ESP32-C6-WROOM-1-N8"))
    )
    (comp (ref "U4")
      (value "ESP32_WROVER_BME680_BME680")
      (footprint "eagle-import:ESP32_WROVER_BME680_PSON80P300X300X100-8N")
      (fields (field (name "MF") "Bosch Sensortec") (field (name "MP") "BME680"))
      (libsource (lib "eagle-import") (part "ESP32_WROVER_BME680_BME680"))
    )
    (comp (ref "U5")
      (value "DS3231SN#")
      (footprint "eagle-import:SOIC127P1032X265-16N")
      (fields (field (name "MF") "Analog Devices"))
      (libsource (lib "eagle-import") (part "DS3231SN#"))
    )
  )
  (nets
    (net (code "1") (name "3V3") (class "Default")
      (node (ref "C18") (pin "+") (pinfunction "+_+") (pintype "passive"))
      (node (ref "C1_BAT2") (pin "1") (pinfunction "1_1") (pintype "passive"))
      (node (ref "C9") (pin "1") (pinfunction "1_1") (pintype "passive"))
      (node (ref "D10") (pin "2") (pinfunction "ANODE_2") (pintype "bidirectional"))
      (node (ref "IC1") (pin "5") (pinfunction "VOUT_5") (pintype "bidirectional"))
      (node (ref "IC2") (pin "2") (pinfunction "VDD_2") (pintype "bidirectional"))
      (node (ref "J1") (pin "P4") (pinfunction "VDD_P4") (pintype "bidirectional"))
      (node (ref "J2") (pin "2") (pinfunction "2_2") (pintype "power_in"))
      (node (ref "Q1") (pin "3") (pinfunction "D_3") (pintype "bidirectional"))
      (node (ref "R1") (pin "2") (pinfunction "2_2") (pintype "passive"))
      (node (ref "R10") (pin "2") (pinfunction "2_2") (pintype "passive"))
      (node (ref "R11") (pin "2") (pinfunction "2_2") (pintype "passive"))
      (node (ref "R12") (pin "2") (pinfunction "2_2") (pintype "passive"))
      (node (ref "R14") (pin "2") (pinfunction "2_2") (pintype "passive"))
      (node (ref "R15") (pin "2") (pinfunction "2_2") (pintype "passive"))
      (node (ref "R19") (pin "2") (pinfunction "2_2") (pintype "passive"))
      (node (ref "R20") (pin "2") (pinfunction "2_2") (pintype "passive"))
      (node (ref "R21") (pin "2") (pinfunction "2_2") (pintype "passive"))
      (node (ref "R7") (pin "2") (pinfunction "2_2") (pintype "passive"))
      (node (ref "R8") (pin "2") (pinfunction "2_2") (pintype "passive"))
      (node (ref "R9") (pin "2") (pinfunction "2_2") (pintype "passive"))
      (node (ref "R_CL1") (pin "2") (pinfunction "2_2") (pintype "passive"))
      (node (ref "TP16") (pin "TP") (pinfunction "TP_TP") (pintype "input"))
      (node (ref "U2") (pin "3") (pinfunction "~{WP}(IO2)_3") (pintype "bidirectional"))
      (node (ref "U2") (pin "7") (pinfunction "~{HOLD}/~{RESET}(IO3)_7") (pintype "bidirectional"))
      (node (ref "U2") (pin "8") (pinfunction "VCC_8") (pintype "power_in"))
      (node (ref "U3") (pin "2") (pinfunction "3V3_2") (pintype "power_in"))
      (node (ref "U5") (pin "2") (pinfunction "VCC_2") (pintype "power_in"))
    )
    (net (code "2") (name "12C_PW") (class "Default")
      (node (ref "C1") (pin "1") (pinfunction "1_1") (pintype "passive"))
      (node (ref "C2") (pin "1") (pinfunction "1_1") (pintype "passive"))
      (node (ref "R3") (pin "2") (pinfunction "2_2") (pintype "passive"))
      (node (ref "R4") (pin "2") (pinfunction "2_2") (pintype "passive"))
      (node (ref "U3") (pin "17") (pinfunction "IO19_17") (pintype "bidirectional"))
      (node (ref "U4") (pin "2") (pinfunction "CSB_2") (pintype "input"))
      (node (ref "U4") (pin "6") (pinfunction "VDDIO_6") (pintype "power_in"))
      (node (ref "U4") (pin "8") (pinfunction "VDD_8") (pintype "power_in"))
    )
    (net (code "3") (name "32KHZ") (class "Default")
      (node (ref "R14") (pin "1") (pinfunction "1_1") (pintype "passive"))
      (node (ref "U3") (pin "9") (pinfunction "IO1_9") (pintype "bidirectional"))
      (node (ref "U5") (pin "1") (pinfunction "32KHZ_1") (pintype "output"))
    )
    (net (code "4") (name "DN") (class "Default")
      (node (ref "D12") (pin "1") (pinfunction "I/O1_1_1") (pintype "bidirectional"))
      (node (ref "J4") (pin "A7") (pinfunction "A7_A7") (pintype "bidirectional"))
      (node (ref "J4") (pin "B7") (pinfunction "B7_B7") (pintype "bidirectional"))
    )
    (net (code "5") (name "DP") (class "Default")
      (node (ref "D12") (pin "3") (pinfunction "I/O2_1_3") (pintype "bidirectional"))
      (node (ref "J4") (pin "A6") (pinfunction "A6_A6") (pintype "bidirectional"))
      (node (ref "J4") (pin "B6") (pinfunction "B6_B6") (pintype "bidirectional"))
    )
    (net (code "6") (name "EPD_3V3") (class "Default")
      (node (ref "C10") (pin "1") (pinfunction "1_1") (pintype "passive"))
      (node (ref "C7") (pin "1") (pinfunction "1_1") (pintype "passive"))
      (node (ref "J3") (pin "15") (pinfunction "15_15") (pintype "bidirectional"))
      (node (ref "J3") (pin "16") (pinfunction "16_16") (pintype "bidirectional"))
      (node (ref "L1") (pin "2") (pinfunction "2_2") (pintype "passive"))
      (node (ref "Q1") (pin "2") (pinfunction "S_2") (pintype "bidirectional"))
      (node (ref "TP17") (pin "TP") (pinfunction "TP_TP") (pintype "input"))
    )
    (net (code "7") (name "EPD_3V3_C") (class "Default")
      (node (ref "Q1") (pin "1") (pinfunction "G_1") (pintype "bidirectional"))
      (node (ref "R_CL1") (pin "1") (pinfunction "1_1") (pintype "passive"))
      (node (ref "TP13") (pin "TP") (pinfunction "TP_TP") (pintype "input"))
      (node (ref "U3") (pin "18") (pinfunction "IO20_18") (pintype "bidirectional"))
    )
    (net (code "8") (name "EPD_BUSY") (class "Default")
      (node (ref "J3") (pin "9") (pinfunction "9_9") (pintype "bidirectional"))
      (node (ref "TP9") (pin "TP") (pinfunction "TP_TP") (pintype "input"))
      (node (ref "U3") (pin "26") (pinfunction "IO3_26") (pintype "bidirectional"))
    )
    (net (code "9") (name "EPD_CS") (class "Default")
      (node (ref "D8") (pin "2") (pinfunction "2_2") (pintype "passive"))
      (node (ref "J3") (pin "12") (pinfunction "12_12") (pintype "bidirectional"))
      (node (ref "R8") (pin "1") (pinfunction "1_1") (pintype "passive"))
      (node (ref "TP10") (pin "TP") (pinfunction "TP_TP") (pintype "input"))
      (node (ref "U3") (pin "11") (pinfunction "IO10_11") (pintype "bidirectional"))
    )
    (net (code "10") (name "EPD_DC") (class "Default")
      (node (ref "J3") (pin "11") (pinfunction "11_11") (pintype "bidirectional"))
      (node (ref "TP11") (pin "TP") (pinfunction "TP_TP") (pintype "input"))
      (node (ref "U3") (pin "5") (pinfunction "IO5_5") (pintype "bidirectional"))
    )
    (net (code "11") (name "EPD_RST") (class "Default")
      (node (ref "J3") (pin "10") (pinfunction "10_10") (pintype "bidirectional"))
      (node (ref "TP12") (pin "TP") (pinfunction "TP_TP") (pintype "input"))
      (node (ref "U3") (pin "21") (pinfunction "IO23_21") (pintype "bidirectional"))
    )
    (net (code "12") (name "FLASH_CS") (class "Default")
      (node (ref "D7") (pin "2") (pinfunction "2_2") (pintype "passive"))
      (node (ref "R9") (pin "1") (pinfunction "1_1") (pintype "passive"))
      (node (ref "U2") (pin "1") (pinfunction "~{CS}_1") (pintype "input"))
      (node (ref "U3") (pin "12") (pinfunction "IO11_12") (pintype "bidirectional"))
    )
    (net (code "13") (name "GDR") (class "Default")
      (node (ref "J3") (pin "2") (pinfunction "2_2") (pintype "bidirectional"))
      (node (ref "Q2") (pin "1") (pinfunction "G_1") (pintype "bidirectional"))
      (node (ref "R5") (pin "2") (pinfunction "2_2") (pintype "passive"))
    )
    (net (code "14") (name "GND") (class "Default")
      (node (ref "C1") (pin "2") (pinfunction "2_2") (pintype "passive"))
      (node (ref "C10") (pin "2") (pinfunction "2_2") (pintype "passive"))
      (node (ref "C11") (pin "2") (pinfunction "2_2") (pintype "passive"))
      (node (ref "C12") (pin "2") (pinfunction "2_2") (pintype "passive"))
      (node (ref "C13") (pin "2") (pinfunction "2_2") (pintype "passive"))
      (node (ref "C14") (pin "2") (pinfunction "2_2") (pintype "passive"))
      (node (ref "C15") (pin "2") (pinfunction "2_2") (pintype "passive"))
      (node (ref "C16") (pin "2") (pinfunction "2_2") (pintype "passive"))
      (node (ref "C17") (pin "2") (pinfunction "2_2") (pintype "passive"))
      (node (ref "C18") (pin "-") (pinfunction "-_-") (pintype "passive"))
      (node (ref "C19") (pin "2") (pinfunction "2_2") (pintype "passive"))
      (node (ref "C1_BAT") (pin "2") (pinfunction "2_2") (pintype "passive"))
      (node (ref "C1_BAT1") (pin "2") (pinfunction "2_2") (pintype "passive"))
      (node (ref "C1_BAT2") (pin "2") (pinfunction "2_2") (pintype "passive"))
      (node (ref "C2") (pin "2") (pinfunction "2_2") (pintype "passive"))
      (node (ref "C20") (pin "2") (pinfunction "2_2") (pintype "passive"))
      (node (ref "C21") (pin "2") (pinfunction "2_2") (pintype "passive"))
      (node (ref "C22") (pin "2") (pinfunction "2_2") (pintype "passive"))
      (node (ref "C23") (pin "2") (pinfunction "2_2") (pintype "passive"))
      (node (ref "C24") (pin "2") (pinfunction "2_2") (pintype "passive"))
      (node (ref "C2_BAT") (pin "2") (pinfunction "2_2") (pintype "passive"))
      (node (ref "C3") (pin "2") (pinfunction "2_2") (pintype "passive"))
      (node (ref "C5") (pin "2") (pinfunction "2_2") (pintype "passive"))
      (node (ref "C6") (pin "2") (pinfunction "2_2") (pintype "passive"))
      (node (ref "C7") (pin "2") (pinfunction "2_2") (pintype "passive"))
      (node (ref "C8") (pin "2") (pinfunction "2_2") (pintype "passive"))
      (node (ref "C9") (pin "2") (pinfunction "2_2") (pintype "passive"))
      (node (ref "D12") (pin "5") (pinfunction "VBUS_5") (pintype "bidirectional"))
      (node (ref "D3") (pin "1") (pinfunction "K_1") (pintype "bidirectional"))
      (node (ref "D4") (pin "1") (pinfunction "1_1") (pintype "passive"))
      (node (ref "D5") (pin "1") (pinfunction "1_1") (pintype "passive"))
      (node (ref "D6") (pin "1") (pinfunction "1_1") (pintype "passive"))
      (node (ref "D7") (pin "1") (pinfunction "1_1") (pintype "passive"))
      (node (ref "D8") (pin "1") (pinfunction "1_1") (pintype "passive"))
      (node (ref "D9") (pin "1") (pinfunction "1_1") (pintype "passive"))
      (node (ref "IC1") (pin "2") (pinfunction "VSS_2") (pintype "bidirectional"))
      (node (ref "IC2") (pin "3") (pinfunction "GND_3") (pintype "bidirectional"))
      (node (ref "J1") (pin "G1") (pinfunction "GND_1_G1") (pintype "bidirectional"))
      (node (ref "J1") (pin "G2") (pinfunction "GND_2_G2") (pintype "bidirectional"))
      (node (ref "J1") (pin "G3") (pinfunction "GND_3_G3") (pintype "bidirectional"))
      (node (ref "J1") (pin "G4") (pinfunction "GND_4_G4") (pintype "bidirectional"))
      (node (ref "J1") (pin "P6") (pinfunction "VSS_P6") (pintype "bidirectional"))
      (node (ref "J2") (pin "1") (pinfunction "1_1") (pintype "power_in"))
      (node (ref "J3") (pin "17") (pinfunction "17_17") (pintype "bidirectional"))
      (node (ref "J3") (pin "8") (pinfunction "8_8") (pintype "bidirectional"))
      (node (ref "J3") (pin "MP1") (pinfunction "MP1_MP1") (pintype "bidirectional"))
      (node (ref "J3") (pin "MP2") (pinfunction "MP2_MP2") (pintype "bidirectional"))
      (node (ref "J4") (pin "A1") (pinfunction "A1_A1") (pintype "bidirectional"))
      (node (ref "J4") (pin "A12") (pinfunction "A12_A12") (pintype "bidirectional"))
      (node (ref "J4") (pin "B1") (pinfunction "B1_B1") (pintype "bidirectional"))
      (node (ref "J4") (pin "B12") (pinfunction "B12_B12") (pintype "bidirectional"))
      (node (ref "J4") (pin "MP1") (pinfunction "MP1_MP1") (pintype "bidirectional"))
      (node (ref "J4") (pin "MP2") (pinfunction "MP2_MP2") (pintype "bidirectional"))
      (node (ref "J4") (pin "MP3") (pinfunction "MP3_MP3") (pintype "bidirectional"))
      (node (ref "J4") (pin "MP4") (pinfunction "MP4_MP4") (pintype "bidirectional"))
      (node (ref "MCP73831") (pin "2") (pinfunction "VSS_2") (pintype "power_in"))
      (node (ref "R16") (pin "1") (pinfunction "1_1") (pintype "passive"))
      (node (ref "R17") (pin "2") (pinfunction "2_2") (pintype "passive"))
      (node (ref "R1_PWRUSB") (pin "1") (pinfunction "1_1") (pintype "passive"))
      (node (ref "R2") (pin "1") (pinfunction "1_1") (pintype "passive"))
      (node (ref "R2_BAT") (pin "1") (pinfunction "1_1") (pintype "passive"))
      (node (ref "R5") (pin "1") (pinfunction "1_1") (pintype "passive"))
      (node (ref "SJ1") (pin "1") (pinfunction "1_1") (pintype "passive"))
      (node (ref "TP4") (pin "TP") (pinfunction "TP_TP") (pintype "input"))
      (node (ref "TP5") (pin "TP") (pinfunction "TP_TP") (pintype "input"))
      (node (ref "U$1") (pin "1") (pinfunction "1_1") (pintype "passive"))
      (node (ref "U$1") (pin "2") (pinfunction "2_2") (pintype "passive"))
      (node (ref "U$2") (pin "1") (pinfunction "1_1") (pintype "passive"))
      (node (ref "U$2") (pin "2") (pinfunction "2_2") (pintype "passive"))
      (node (ref "U$3") (pin "1") (pinfunction "1_1") (pintype "passive"))
      (node (ref "U$3") (pin "2") (pinfunction "2_2") (pintype "passive"))
      (node (ref "U1") (pin "1") (pinfunction "CTG_1") (pintype "power_in"))
      (node (ref "U1") (pin "4") (pinfunction "GND_4") (pintype "power_in"))
      (node (ref "U1") (pin "6") (pinfunction "QSTRT_6") (pintype "input"))
      (node (ref "U1") (pin "9") (pinfunction "EP_9") (pintype "power_in"))
      (node (ref "U2") (pin "4") (pinfunction "GND_4") (pintype "power_in"))
      (node (ref "U2") (pin "9") (pinfunction "EXP_9") (pintype "passive"))
      (node (ref "U3") (pin "1") (pinfunction "GND_1") (pintype "power_in"))
      (node (ref "U3") (pin "28") (pinfunction "GND_28") (pintype "power_in"))
      (node (ref "U3") (pin "29_1") (pinfunction "GND_29_1") (pintype "power_in"))
      (node (ref "U3") (pin "29_2") (pinfunction "GND_29_2") (pintype "power_in"))
      (node (ref "U3") (pin "29_3") (pinfunction "GND_29_3") (pintype "power_in"))
      (node (ref "U3") (pin "29_4") (pinfunction "GND_29_4") (pintype "power_in"))
      (node (ref "U3") (pin "29_5") (pinfunction "GND_29_5") (pintype "power_in"))
      (node (ref "U3") (pin "29_6") (pinfunction "GND_29_6") (pintype "power_in"))
      (node (ref "U3") (pin "29_7") (pinfunction "GND_29_7") (pintype "power_in"))
      (node (ref "U3") (pin "29_8") (pinfunction "GND_29_8") (pintype "power_in"))
      (node (ref "U3") (pin "29_9") (pinfunction "GND_29_9") (pintype "power_in"))
      (node (ref "U4") (pin "1") (pinfunction "GND_1") (pintype "power_in"))
      (node (ref "U4") (pin "5") (pinfunction "SDO_5") (pintype "bidirectional"))
      (node (ref "U4") (pin "7") (pinfunction "GND_7") (pintype "power_in"))
      (node (ref "U5") (pin "13") (pinfunction "GND_13") (pintype "power_in"))
    )
    (net (code "15") (name "GPIO8") (class "Default")
      (node (ref "R1") (pin "1") (pinfunction "1_1") (pintype "passive"))
      (node (ref "U3") (pin "10") (pinfunction "IO8_10") (pintype "bidirectional"))
    )
    (net (code "16") (name "INT_RTC") (class "Default")
      (node (ref "R15") (pin "1") (pinfunction "1_1") (pintype "passive"))
      (node (ref "TP15") (pin "TP") (pinfunction "TP_TP") (pintype "input"))
      (node (ref "U3") (pin "8") (pinfunction "IO0_8") (pintype "bidirectional"))
      (node (ref "U5") (pin "3") (pinfunction "SQW/~{INT}_3") (pintype "output"))
    )
    (net (code "17") (name "IO{slash}BOOT") (class "Default")
      (node (ref "C23") (pin "1") (pinfunction "1_1") (pintype "passive"))
      (node (ref "R19") (pin "1") (pinfunction "1_1") (pintype "passive"))
      (node (ref "U$2") (pin "3") (pinfunction "3_3") (pintype "passive"))
      (node (ref "U$2") (pin "4") (pinfunction "4_4") (pintype "passive"))
      (node (ref "U3") (pin "15") (pinfunction "IO9_15") (pintype "bidirectional"))
    )
    (net (code "18") (name "IO{slash}CHANGE") (class "Default")
      (node (ref "C24") (pin "1") (pinfunction "1_1") (pintype "passive"))
      (node (ref "R21") (pin "1") (pinfunction "1_1") (pintype "passive"))
      (node (ref "U$3") (pin "3") (pinfunction "3_3") (pintype "passive"))
      (node (ref "U$3") (pin "4") (pinfunction "4_4") (pintype "passive"))
      (node (ref "U3") (pin "23") (pinfunction "IO15_23") (pintype "bidirectional"))
    )
    (net (code "19") (name "MISO") (class "Default")
      (node (ref "D4") (pin "2") (pinfunction "2_2") (pintype "passive"))
      (node (ref "J1") (pin "P7") (pinfunction "DAT0_P7") (pintype "bidirectional"))
      (node (ref "R12") (pin "1") (pinfunction "1_1") (pintype "passive"))
      (node (ref "TP6") (pin "TP") (pinfunction "TP_TP") (pintype "input"))
      (node (ref "U2") (pin "2") (pinfunction "DO(IO1)_2") (pintype "bidirectional"))
      (node (ref "U3") (pin "27") (pinfunction "IO2_27") (pintype "bidirectional"))
    )
    (net (code "20") (name "MOSI") (class "Default")
      (node (ref "D5") (pin "2") (pinfunction "2_2") (pintype "passive"))
      (node (ref "J1") (pin "P3") (pinfunction "CMD_P3") (pintype "bidirectional"))
      (node (ref "J3") (pin "14") (pinfunction "14_14") (pintype "bidirectional"))
      (node (ref "R11") (pin "1") (pinfunction "1_1") (pintype "passive"))
      (node (ref "TP7") (pin "TP") (pinfunction "TP_TP") (pintype "input"))
      (node (ref "U2") (pin "5") (pinfunction "DI(IO0)_5") (pintype "bidirectional"))
      (node (ref "U3") (pin "7") (pinfunction "IO7_7") (pintype "bidirectional"))
    )
    (net (code "21") (name "N$27") (class "Default")
      (node (ref "C19") (pin "1") (pinfunction "1_1") (pintype "passive"))
      (node (ref "C20") (pin "1") (pinfunction "1_1") (pintype "passive"))
    )
    (net (code "22") (name "Net-(C6-Pad1)") (class "Default")
      (node (ref "C6") (pin "1") (pinfunction "1_1") (pintype "passive"))
      (node (ref "J3") (pin "5") (pinfunction "5_5") (pintype "bidirectional"))
    )
    (net (code "23") (name "Net-(C8-Pad1)") (class "Default")
      (node (ref "C8") (pin "1") (pinfunction "1_1") (pintype "passive"))
      (node (ref "J3") (pin "4") (pinfunction "4_4") (pintype "bidirectional"))
    )
    (net (code "24") (name "Net-(C11-Pad1)") (class "Default")
      (node (ref "C11") (pin "1") (pinfunction "1_1") (pintype "passive"))
      (node (ref "J3") (pin "18") (pinfunction "18_18") (pintype "bidirectional"))
    )
    (net (code "25") (name "Net-(C12-Pad1)") (class "Default")
      (node (ref "C12") (pin "1") (pinfunction "1_1") (pintype "passive"))
      (node (ref "J3") (pin "19") (pinfunction "19_19") (pintype "bidirectional"))
    )
    (net (code "26") (name "Net-(C13-Pad1)") (class "Default")
      (node (ref "C13") (pin "1") (pinfunction "1_1") (pintype "passive"))
      (node (ref "J3") (pin "20") (pinfunction "20_20") (pintype "bidirectional"))
    )
    (net (code "27") (name "Net-(C15-Pad1)") (class "Default")
      (node (ref "C15") (pin "1") (pinfunction "1_1") (pintype "passive"))
      (node (ref "J3") (pin "22") (pinfunction "22_22") (pintype "bidirectional"))
    )
    (net (code "28") (name "Net-(C17-Pad1)") (class "Default")
      (node (ref "C17") (pin "1") (pinfunction "1_1") (pintype "passive"))
      (node (ref "J3") (pin "24") (pinfunction "24_24") (pintype "bidirectional"))
    )
    (net (code "29") (name "Net-(CHG_LED-PadC)") (class "Default")
      (node (ref "CHG_LED") (pin "C") (pinfunction "C_C") (pintype "passive"))
      (node (ref "R1_BAT") (pin "1") (pinfunction "1_1") (pintype "passive"))
    )
    (net (code "30") (name "Net-(D2-K)") (class "Default")
      (node (ref "C4") (pin "1") (pinfunction "1_1") (pintype "passive"))
      (node (ref "D2") (pin "1") (pinfunction "K_1") (pintype "bidirectional"))
      (node (ref "D3") (pin "2") (pinfunction "A_2") (pintype "bidirectional"))
    )
    (net (code "31") (name "Net-(D10-CATHODE)") (class "Default")
      (node (ref "D10") (pin "1") (pinfunction "CATHODE_1") (pintype "bidirectional"))
      (node (ref "R13") (pin "1") (pinfunction "1_1") (pintype "passive"))
    )
    (net (code "32") (name "Net-(D11-CATHODE)") (class "Default")
      (node (ref "C1_BAT1") (pin "1") (pinfunction "1_1") (pintype "passive"))
      (node (ref "D11") (pin "1") (pinfunction "CATHODE_1") (pintype "bidirectional"))
      (node (ref "IC1") (pin "1") (pinfunction "VIN_1") (pintype "bidirectional"))
      (node (ref "IC1") (pin "3") (pinfunction "CE_3") (pintype "bidirectional"))
      (node (ref "Q3") (pin "2") (pinfunction "S_2") (pintype "bidirectional"))
    )
    (net (code "33") (name "Net-(IC2-CT)") (class "Default")
      (node (ref "C21") (pin "1") (pinfunction "1_1") (pintype "passive"))
      (node (ref "IC2") (pin "5") (pinfunction "CT_5") (pintype "bidirectional"))
    )
    (net (code "34") (name "Net-(J4-PadA5)") (class "Default")
      (node (ref "J4") (pin "A5") (pinfunction "A5_A5") (pintype "bidirectional"))
      (node (ref "R16") (pin "2") (pinfunction "2_2") (pintype "passive"))
    )
    (net (code "35") (name "Net-(J4-PadB5)") (class "Default")
      (node (ref "J4") (pin "B5") (pinfunction "B5_B5") (pintype "bidirectional"))
      (node (ref "R17") (pin "1") (pinfunction "1_1") (pintype "passive"))
    )
    (net (code "36") (name "Net-(MCP73831-PROG)") (class "Default")
      (node (ref "MCP73831") (pin "5") (pinfunction "PROG_5") (pintype "input"))
      (node (ref "R2_BAT") (pin "2") (pinfunction "2_2") (pintype "passive"))
    )
    (net (code "37") (name "Net-(MCP73831-STAT)") (class "Default")
      (node (ref "MCP73831") (pin "1") (pinfunction "STAT_1") (pintype "output"))
      (node (ref "R1_BAT") (pin "2") (pinfunction "2_2") (pintype "passive"))
    )
    (net (code "38") (name "PREVGH") (class "Default")
      (node (ref "C14") (pin "1") (pinfunction "1_1") (pintype "passive"))
      (node (ref "D1") (pin "1") (pinfunction "K_1") (pintype "bidirectional"))
      (node (ref "J3") (pin "21") (pinfunction "21_21") (pintype "bidirectional"))
    )
    (net (code "39") (name "PREVGL") (class "Default")
      (node (ref "C16") (pin "1") (pinfunction "1_1") (pintype "passive"))
      (node (ref "D2") (pin "2") (pinfunction "A_2") (pintype "bidirectional"))
      (node (ref "J3") (pin "23") (pinfunction "23_23") (pintype "bidirectional"))
    )
    (net (code "40") (name "RESE") (class "Default")
      (node (ref "J3") (pin "3") (pinfunction "3_3") (pintype "bidirectional"))
      (node (ref "Q2") (pin "2") (pinfunction "S_2") (pintype "bidirectional"))
      (node (ref "R6") (pin "2") (pinfunction "2_2") (pintype "passive"))
    )
    (net (code "41") (name "RESE'") (class "Default")
      (node (ref "R6") (pin "1") (pinfunction "1_1") (pintype "passive"))
    )
    (net (code "42") (name "RESET") (class "Default")
      (node (ref "C22") (pin "1") (pinfunction "1_1") (pintype "passive"))
      (node (ref "IC2") (pin "1") (pinfunction "VOUT_1") (pintype "bidirectional"))
      (node (ref "R2") (pin "2") (pinfunction "2_2") (pintype "passive"))
      (node (ref "R20") (pin "1") (pinfunction "1_1") (pintype "passive"))
      (node (ref "SJ1") (pin "2") (pinfunction "2_2") (pintype "passive"))
      (node (ref "U$1") (pin "3") (pinfunction "3_3") (pintype "passive"))
      (node (ref "U$1") (pin "4") (pinfunction "4_4") (pintype "passive"))
      (node (ref "U3") (pin "3") (pinfunction "EN_3") (pintype "input"))
    )
    (net (code "43") (name "RTC_RST") (class "Default")
      (node (ref "U3") (pin "16") (pinfunction "IO18_16") (pintype "bidirectional"))
      (node (ref "U5") (pin "4") (pinfunction "~{RST}_4") (pintype "input"))
    )
    (net (code "44") (name "RX") (class "Default")
      (node (ref "TP2") (pin "TP") (pinfunction "TP_TP") (pintype "input"))
      (node (ref "U3") (pin "24") (pinfunction "RXD0/GPIO17_24") (pintype "bidirectional"))
    )
    (net (code "45") (name "SCK") (class "Default")
      (node (ref "D6") (pin "2") (pinfunction "2_2") (pintype "passive"))
      (node (ref "J1") (pin "P5") (pinfunction "CLK_P5") (pintype "bidirectional"))
      (node (ref "J3") (pin "13") (pinfunction "13_13") (pintype "bidirectional"))
      (node (ref "R10") (pin "1") (pinfunction "1_1") (pintype "passive"))
      (node (ref "TP8") (pin "TP") (pinfunction "TP_TP") (pintype "input"))
      (node (ref "U2") (pin "6") (pinfunction "CLK_6") (pintype "input"))
      (node (ref "U3") (pin "6") (pinfunction "IO6_6") (pintype "bidirectional"))
    )
    (net (code "46") (name "SCL") (class "Default")
      (node (ref "J2") (pin "4") (pinfunction "4_4") (pintype "passive"))
      (node (ref "R3") (pin "1") (pinfunction "1_1") (pintype "passive"))
      (node (ref "U1") (pin "7") (pinfunction "SCL_7") (pintype "input"))
      (node (ref "U3") (pin "20") (pinfunction "IO22_20") (pintype "bidirectional"))
      (node (ref "U4") (pin "4") (pinfunction "SCK_4") (pintype "input"))
      (node (ref "U5") (pin "16") (pinfunction "SCL_16") (pintype "input"))
    )
    (net (code "47") (name "SDA") (class "Default")
      (node (ref "J2") (pin "3") (pinfunction "3_3") (pintype "passive"))
      (node (ref "R4") (pin "1") (pinfunction "1_1") (pintype "passive"))
      (node (ref "U1") (pin "8") (pinfunction "SDA_8") (pintype "bidirectional"))
      (node (ref "U3") (pin "19") (pinfunction "IO21_19") (pintype "bidirectional"))
      (node (ref "U4") (pin "3") (pinfunction "SDI_3") (pintype "bidirectional"))
      (node (ref "U5") (pin "15") (pinfunction "SDA_15") (pintype "bidirectional"))
    )
    (net (code "48") (name "SRC") (class "Default")
      (node (ref "C4") (pin "2") (pinfunction "2_2") (pintype "passive"))
      (node (ref "D1") (pin "2") (pinfunction "A_2") (pintype "bidirectional"))
      (node (ref "L1") (pin "1") (pinfunction "1_1") (pintype "passive"))
      (node (ref "Q2") (pin "3") (pinfunction "D_3") (pintype "bidirectional"))
    )
    (net (code "49") (name "SS_SD") (class "Default")
      (node (ref "D9") (pin "2") (pinfunction "2_2") (pintype "passive"))
      (node (ref "J1") (pin "P2") (pinfunction "CD/DAT3_P2") (pintype "bidirectional"))
      (node (ref "R7") (pin "1") (pinfunction "1_1") (pintype "passive"))
      (node (ref "U3") (pin "4") (pinfunction "IO4_4") (pintype "bidirectional"))
    )
    (net (code "50") (name "TX") (class "Default")
      (node (ref "TP1") (pin "TP") (pinfunction "TP_TP") (pintype "input"))
      (node (ref "U3") (pin "25") (pinfunction "TXD0/GPIO16_25") (pintype "bidirectional"))
    )
    (net (code "51") (name "USB_D+") (class "Default")
      (node (ref "D12") (pin "4") (pinfunction "I/O2_2_4") (pintype "bidirectional"))
      (node (ref "U3") (pin "14") (pinfunction "IO13_14") (pintype "bidirectional"))
    )
    (net (code "52") (name "USB_D-") (class "Default")
      (node (ref "D12") (pin "6") (pinfunction "I/O1_2_6") (pintype "bidirectional"))
      (node (ref "U3") (pin "13") (pinfunction "IO12_13") (pintype "bidirectional"))
    )
    (net (code "53") (name "VBAT") (class "Default")
      (node (ref "C2_BAT") (pin "1") (pinfunction "1_1") (pintype "passive"))
      (node (ref "MCP73831") (pin "3") (pinfunction "VBAT_3") (pintype "power_in"))
      (node (ref "Q3") (pin "3") (pinfunction "D_3") (pintype "bidirectional"))
      (node (ref "TP3") (pin "TP") (pinfunction "TP_TP") (pintype "input"))
      (node (ref "U1") (pin "2") (pinfunction "CELL_2") (pintype "power_in"))
      (node (ref "U1") (pin "3") (pinfunction "VDD_3") (pintype "power_in"))
    )
    (net (code "54") (name "VBUS") (class "Default")
      (node (ref "C1_BAT") (pin "1") (pinfunction "1_1") (pintype "passive"))
      (node (ref "CHG_LED") (pin "A") (pinfunction "A_A") (pintype "passive"))
      (node (ref "D11") (pin "2") (pinfunction "ANODE_2") (pintype "bidirectional"))
      (node (ref "D12") (pin "2") (pinfunction "GND_2") (pintype "bidirectional"))
      (node (ref "MCP73831") (pin "4") (pinfunction "VIN_4") (pintype "power_in"))
      (node (ref "Q3") (pin "1") (pinfunction "G_1") (pintype "bidirectional"))
      (node (ref "R18") (pin "2") (pinfunction "2_2") (pintype "passive"))
      (node (ref "R1_PWRUSB") (pin "2") (pinfunction "2_2") (pintype "passive"))
      (node (ref "TP14") (pin "TP") (pinfunction "TP_TP") (pintype "input"))
    )
    (net (code "55") (name "VRTC") (class "Default")
      (node (ref "C3") (pin "1") (pinfunction "1_1") (pintype "passive"))
      (node (ref "C5") (pin "1") (pinfunction "1_1") (pintype "passive"))
      (node (ref "R13") (pin "2") (pinfunction "2_2") (pintype "passive"))
      (node (ref "U5") (pin "14") (pinfunction "VBAT_14") (pintype "power_in"))
    )
    (net (code "56") (name "VUSB") (class "Default")
      (node (ref "J4") (pin "A4") (pinfunction "A4_A4") (pintype "bidirectional"))
      (node (ref "J4") (pin "A9") (pinfunction "A9_A9") (pintype "bidirectional"))
      (node (ref "J4") (pin "B4") (pinfunction "B4_B4") (pintype "bidirectional"))
      (node (ref "J4") (pin "B9") (pinfunction "B9_B9") (pintype "bidirectional"))
      (node (ref "R18") (pin "1") (pinfunction "1_1") (pintype "passive"))
    )
    (net (code "57") (name "unconnected-(IC1-NC-Pad4)") (class "Default")
      (node (ref "IC1") (pin "4") (pinfunction "NC_4") (pintype "no_connect"))
    )
    (net (code "58") (name "unconnected-(IC2-NC-Pad4)") (class "Default")
      (node (ref "IC2") (pin "4") (pinfunction "NC_4") (pintype "no_connect"))
    )
    (net (code "59") (name "unconnected-(J1-DAT1-PadP8)") (class "Default")
      (node (ref "J1") (pin "P8") (pinfunction "DAT1_P8") (pintype "bidirectional"))
    )
    (net (code "60") (name "unconnected-(J1-DAT2-PadP1)") (class "Default")
      (node (ref "J1") (pin "P1") (pinfunction "DAT2_P1") (pintype "bidirectional"))
    )
    (net (code "61") (name "unconnected-(J1-DETECTION_1-PadS1)") (class "Default")
      (node (ref "J1") (pin "S1") (pinfunction "DETECTION_1_S1") (pintype "bidirectional"))
    )
    (net (code "62") (name "unconnected-(J1-DETECTION_2-PadS2)") (class "Default")
      (node (ref "J1") (pin "S2") (pinfunction "DETECTION_2_S2") (pintype "bidirectional"))
    )
    (net (code "63") (name "unconnected-(J3-Pad1)") (class "Default")
      (node (ref "J3") (pin "1") (pinfunction "1_1") (pintype "bidirectional"))
    )
    (net (code "64") (name "unconnected-(J3-Pad6)") (class "Default")
      (node (ref "J3") (pin "6") (pinfunction "6_6") (pintype "bidirectional"))
    )
    (net (code "65") (name "unconnected-(J3-Pad7)") (class "Default")
      (node (ref "J3") (pin "7") (pinfunction "7_7") (pintype "bidirectional"))
    )
    (net (code "66") (name "unconnected-(J4-PadA8)") (class "Default")
      (node (ref "J4") (pin "A8") (pinfunction "A8_A8") (pintype "bidirectional"))
    )
    (net (code "67") (name "unconnected-(J4-PadB8)") (class "Default")
      (node (ref "J4") (pin "B8") (pinfunction "B8_B8") (pintype "bidirectional"))
    )
    (net (code "68") (name "unconnected-(U1-~{ALERT}-Pad5)") (class "Default")
      (node (ref "U1") (pin "5") (pinfunction "~{ALERT}_5") (pintype "output"))
    )
    (net (code "69") (name "unconnected-(U3-NC-Pad22)") (class "Default")
      (node (ref "U3") (pin "22") (pinfunction "NC_22") (pintype "no_connect"))
    )
  )
)
